# TSOC_Teensy3X.net
KiCad netlist of a schematic drawn in EAGLE
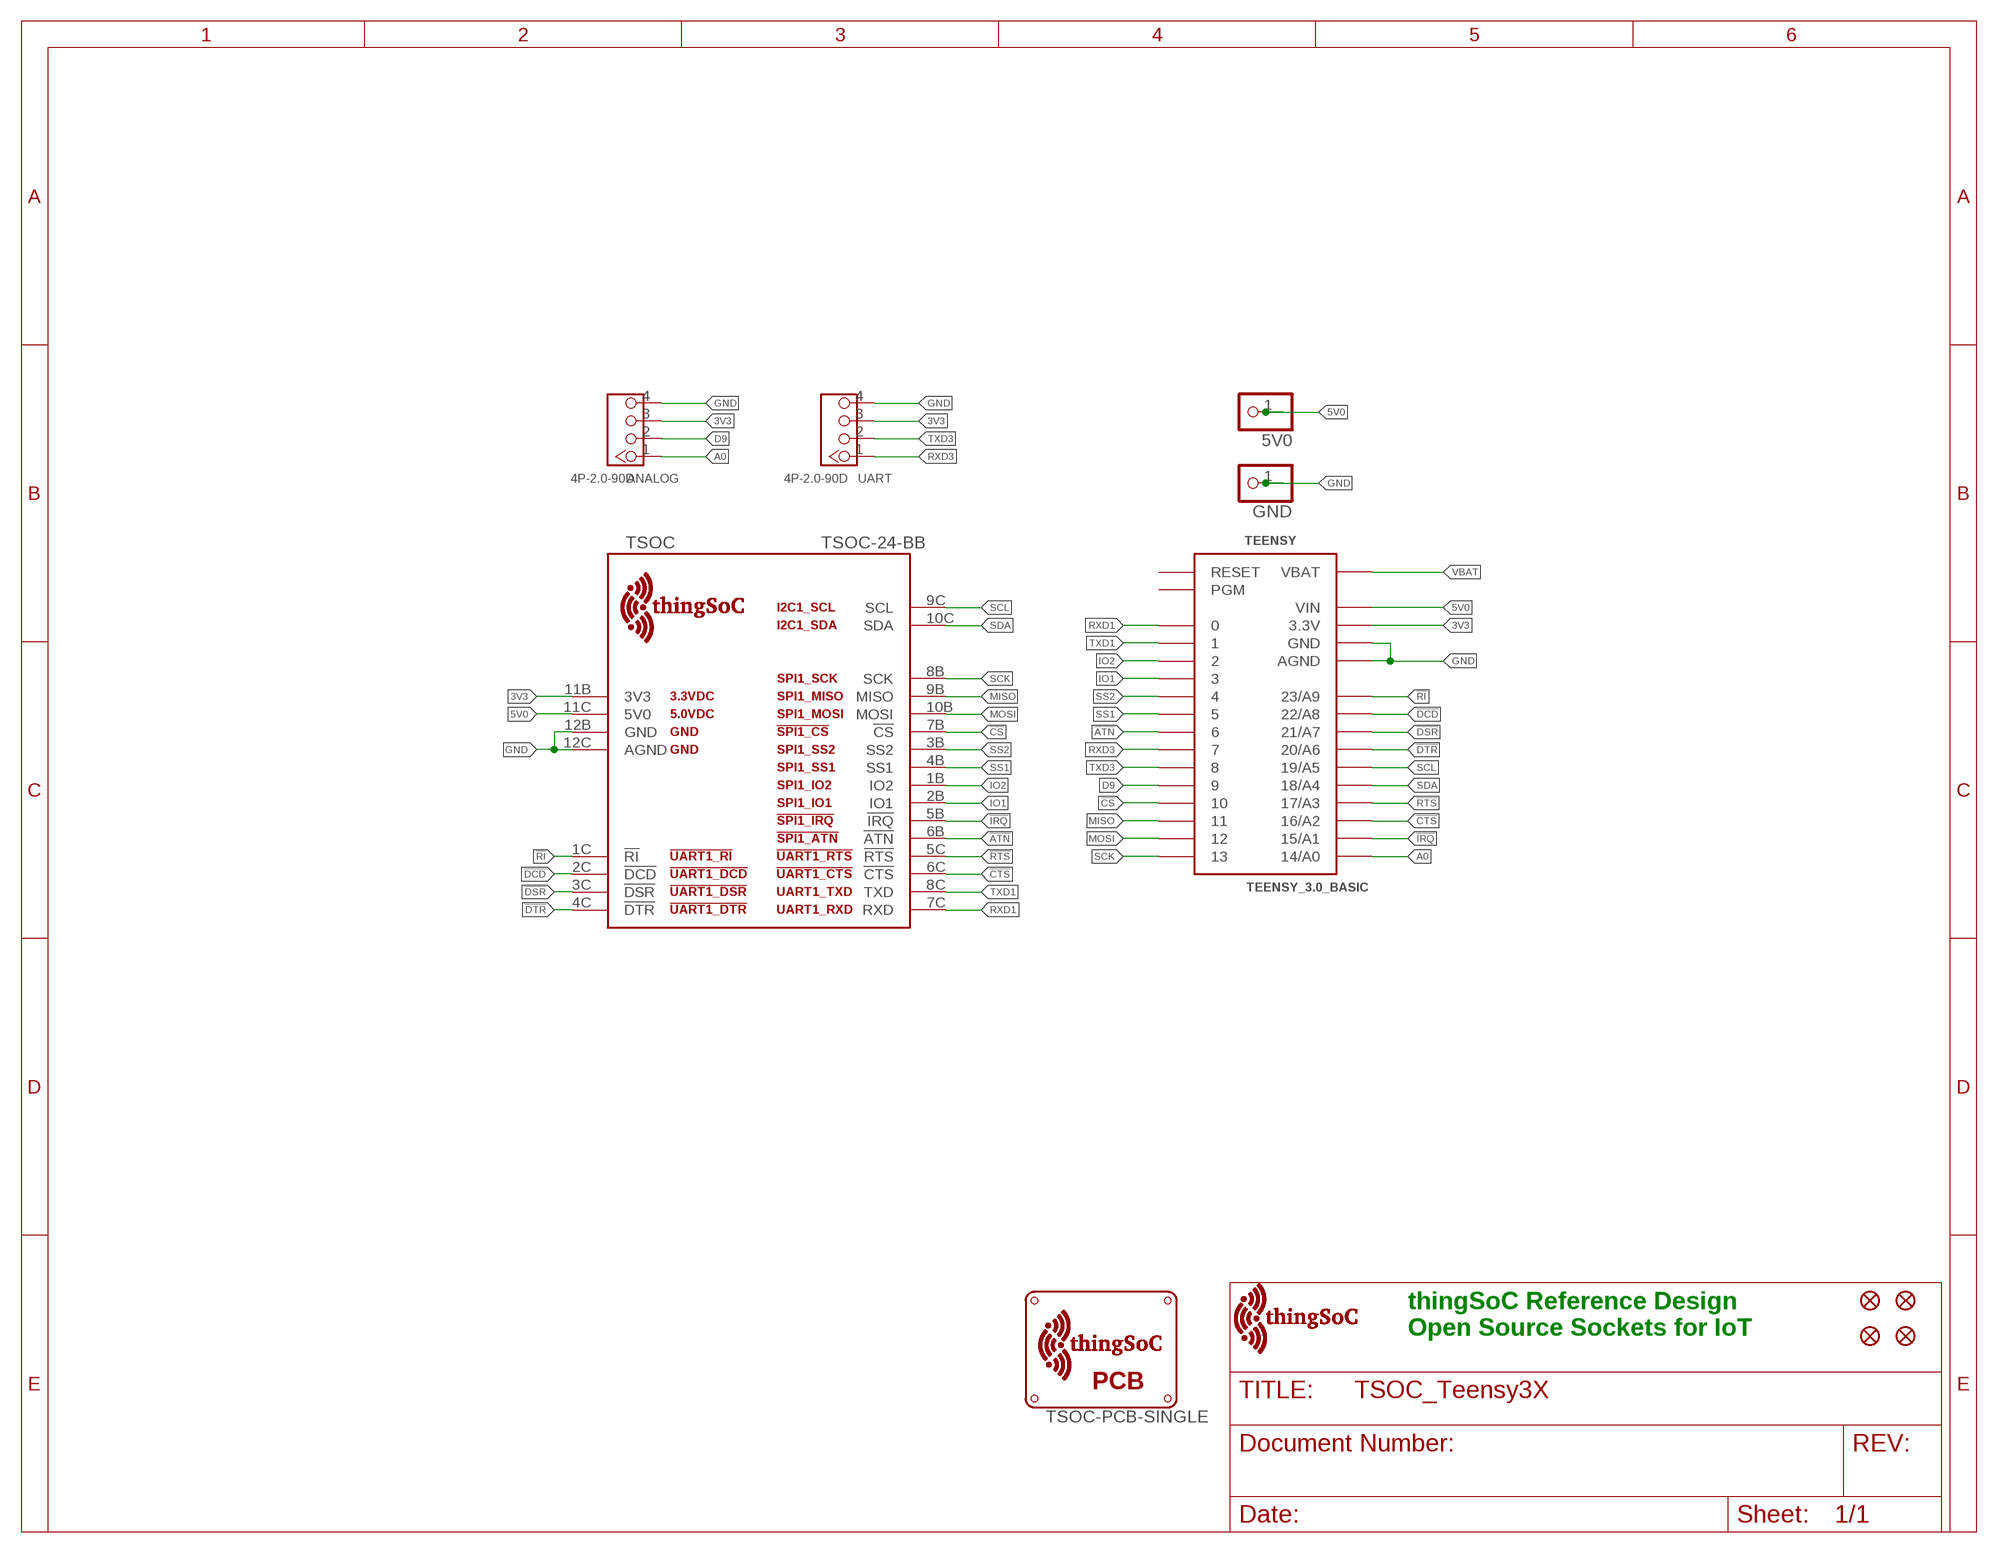
[diagram p0: schematic, sheet 1]

(export (version "E")
  (design (tool "Eeschema 10.0.6"))
  (components
    (comp (ref "5V0")
      (value "WPAD-1-PTH")
      (footprint "eagle-import:WPAD-1-PTH-2.54")
      (libsource (lib "eagle-import") (part "WPAD-1-PTH"))
    )
    (comp (ref "ANALOG")
      (value "4P-2.0-90D")
      (footprint "eagle-import:HW4-2.0-90D")
      (libsource (lib "eagle-import") (part "GROVE-CONNECTOR-DIP-90D(4P-2.0)"))
    )
    (comp (ref "FID1")
      (value "FIDUCIALUFIDUCIAL")
      (footprint "eagle-import:MICRO-FIDUCIAL")
      (libsource (lib "eagle-import") (part "FIDUCIALUFIDUCIAL"))
    )
    (comp (ref "FID2")
      (value "FIDUCIALUFIDUCIAL")
      (footprint "eagle-import:MICRO-FIDUCIAL")
      (libsource (lib "eagle-import") (part "FIDUCIALUFIDUCIAL"))
    )
    (comp (ref "FID3")
      (value "FIDUCIALUFIDUCIAL")
      (footprint "eagle-import:MICRO-FIDUCIAL")
      (libsource (lib "eagle-import") (part "FIDUCIALUFIDUCIAL"))
    )
    (comp (ref "FID4")
      (value "FIDUCIALUFIDUCIAL")
      (footprint "eagle-import:MICRO-FIDUCIAL")
      (libsource (lib "eagle-import") (part "FIDUCIALUFIDUCIAL"))
    )
    (comp (ref "GND")
      (value "WPAD-1-PTH")
      (footprint "eagle-import:WPAD-1-PTH-2.54")
      (libsource (lib "eagle-import") (part "WPAD-1-PTH"))
    )
    (comp (ref "TEENSY")
      (value "TEENSY_3.0_BASIC")
      (footprint "eagle-import:TEENSY_3.0_BASIC")
      (libsource (lib "eagle-import") (part "TEENSY_3.0_BASIC"))
    )
    (comp (ref "TSOC")
      (value "TSOC-24-BB")
      (footprint "eagle-import:TSOC-BB-S24")
      (libsource (lib "eagle-import") (part "TSOC-24-BB"))
    )
    (comp (ref "U$2")
      (value "TSOC-PCB-SINGLE")
      (footprint "eagle-import:TSOC-BB-BRD-DIM")
      (libsource (lib "eagle-import") (part "TSOC-PCB-SINGLE"))
    )
    (comp (ref "U$5")
      (value "TSOC-LOGO-LRG")
      (footprint "eagle-import:TSOC-LOGO-LRG")
      (libsource (lib "eagle-import") (part "TSOC-LOGO-LRG"))
    )
    (comp (ref "UART")
      (value "4P-2.0-90D")
      (footprint "eagle-import:HW4-2.0-90D")
      (libsource (lib "eagle-import") (part "GROVE-CONNECTOR-DIP-90D(4P-2.0)"))
    )
  )
  (nets
    (net (code "1") (name "/~{ATN}") (class "Default")
      (node (ref "TEENSY") (pin "6") (pinfunction "6_6") (pintype "bidirectional"))
      (node (ref "TSOC") (pin "6B") (pinfunction "~{ATN}_6B") (pintype "bidirectional"))
    )
    (net (code "2") (name "/~{CS}") (class "Default")
      (node (ref "TEENSY") (pin "10") (pinfunction "10_10") (pintype "bidirectional"))
      (node (ref "TSOC") (pin "7B") (pinfunction "~{CS}_7B") (pintype "bidirectional"))
    )
    (net (code "3") (name "/~{CTS}") (class "Default")
      (node (ref "TEENSY") (pin "16/A2") (pinfunction "16/A2_16/A2") (pintype "bidirectional"))
      (node (ref "TSOC") (pin "6C") (pinfunction "~{CTS}_6C") (pintype "bidirectional"))
    )
    (net (code "4") (name "/~{DCD}") (class "Default")
      (node (ref "TEENSY") (pin "22/A8") (pinfunction "22/A8_22/A8") (pintype "bidirectional"))
      (node (ref "TSOC") (pin "2C") (pinfunction "~{DCD}_2C") (pintype "bidirectional"))
    )
    (net (code "5") (name "/~{DSR}") (class "Default")
      (node (ref "TEENSY") (pin "21/A7") (pinfunction "21/A7_21/A7") (pintype "bidirectional"))
      (node (ref "TSOC") (pin "3C") (pinfunction "~{DSR}_3C") (pintype "bidirectional"))
    )
    (net (code "6") (name "/~{DTR}") (class "Default")
      (node (ref "TEENSY") (pin "20/A6") (pinfunction "20/A6_20/A6") (pintype "bidirectional"))
      (node (ref "TSOC") (pin "4C") (pinfunction "~{DTR}_4C") (pintype "bidirectional"))
    )
    (net (code "7") (name "/~{IRQ}") (class "Default")
      (node (ref "TEENSY") (pin "15/A1") (pinfunction "15/A1_15/A1") (pintype "bidirectional"))
      (node (ref "TSOC") (pin "5B") (pinfunction "~{IRQ}_5B") (pintype "bidirectional"))
    )
    (net (code "8") (name "/~{RI}") (class "Default")
      (node (ref "TEENSY") (pin "23/A9") (pinfunction "23/A9_23/A9") (pintype "bidirectional"))
      (node (ref "TSOC") (pin "1C") (pinfunction "~{RI}_1C") (pintype "bidirectional"))
    )
    (net (code "9") (name "/~{RTS}") (class "Default")
      (node (ref "TEENSY") (pin "17/A3") (pinfunction "17/A3_17/A3") (pintype "bidirectional"))
      (node (ref "TSOC") (pin "5C") (pinfunction "~{RTS}_5C") (pintype "bidirectional"))
    )
    (net (code "10") (name "3V3") (class "Default")
      (node (ref "ANALOG") (pin "3") (pinfunction "3_3") (pintype "bidirectional"))
      (node (ref "TEENSY") (pin "3.3V") (pinfunction "3.3V_3.3V") (pintype "power_in"))
      (node (ref "TEENSY") (pin "3.3V1") (pinfunction "3.3V_3.3V1") (pintype "power_in"))
      (node (ref "TSOC") (pin "11B") (pinfunction "3V3_11B") (pintype "bidirectional"))
      (node (ref "UART") (pin "3") (pinfunction "3_3") (pintype "bidirectional"))
    )
    (net (code "11") (name "5V0") (class "Default")
      (node (ref "5V0") (pin "1") (pinfunction "1_1") (pintype "passive"))
      (node (ref "TEENSY") (pin "VIN") (pinfunction "VIN_VIN") (pintype "power_in"))
      (node (ref "TSOC") (pin "11C") (pinfunction "5V0_11C") (pintype "bidirectional"))
    )
    (net (code "12") (name "A0") (class "Default")
      (node (ref "ANALOG") (pin "1") (pinfunction "1_1") (pintype "bidirectional"))
      (node (ref "TEENSY") (pin "14/A0") (pinfunction "14/A0_14/A0") (pintype "bidirectional"))
    )
    (net (code "13") (name "D9") (class "Default")
      (node (ref "ANALOG") (pin "2") (pinfunction "2_2") (pintype "bidirectional"))
      (node (ref "TEENSY") (pin "9") (pinfunction "9_9") (pintype "bidirectional"))
    )
    (net (code "14") (name "GND") (class "Default")
      (node (ref "ANALOG") (pin "4") (pinfunction "4_4") (pintype "bidirectional"))
      (node (ref "GND") (pin "1") (pinfunction "1_1") (pintype "passive"))
      (node (ref "TEENSY") (pin "AGND") (pinfunction "AGND_AGND") (pintype "power_in"))
      (node (ref "TEENSY") (pin "GND") (pinfunction "GND_GND") (pintype "power_in"))
      (node (ref "TEENSY") (pin "GND1") (pinfunction "GND_GND1") (pintype "power_in"))
      (node (ref "TSOC") (pin "12B") (pinfunction "GND_12B") (pintype "bidirectional"))
      (node (ref "TSOC") (pin "12C") (pinfunction "AGND_12C") (pintype "bidirectional"))
      (node (ref "UART") (pin "4") (pinfunction "4_4") (pintype "bidirectional"))
    )
    (net (code "15") (name "IO1") (class "Default")
      (node (ref "TEENSY") (pin "3") (pinfunction "3_3") (pintype "bidirectional"))
      (node (ref "TSOC") (pin "2B") (pinfunction "IO1_2B") (pintype "bidirectional"))
    )
    (net (code "16") (name "IO2") (class "Default")
      (node (ref "TEENSY") (pin "2") (pinfunction "2_2") (pintype "bidirectional"))
      (node (ref "TSOC") (pin "1B") (pinfunction "IO2_1B") (pintype "bidirectional"))
    )
    (net (code "17") (name "MISO") (class "Default")
      (node (ref "TEENSY") (pin "11") (pinfunction "11_11") (pintype "bidirectional"))
      (node (ref "TSOC") (pin "9B") (pinfunction "MISO_9B") (pintype "bidirectional"))
    )
    (net (code "18") (name "MOSI") (class "Default")
      (node (ref "TEENSY") (pin "12") (pinfunction "12_12") (pintype "bidirectional"))
      (node (ref "TSOC") (pin "10B") (pinfunction "MOSI_10B") (pintype "bidirectional"))
    )
    (net (code "19") (name "RXD1") (class "Default")
      (node (ref "TEENSY") (pin "0") (pinfunction "0_0") (pintype "bidirectional"))
      (node (ref "TSOC") (pin "7C") (pinfunction "RXD_7C") (pintype "bidirectional"))
    )
    (net (code "20") (name "RXD3") (class "Default")
      (node (ref "TEENSY") (pin "7") (pinfunction "7_7") (pintype "bidirectional"))
      (node (ref "UART") (pin "1") (pinfunction "1_1") (pintype "bidirectional"))
    )
    (net (code "21") (name "SCK") (class "Default")
      (node (ref "TEENSY") (pin "13") (pinfunction "13_13") (pintype "bidirectional"))
      (node (ref "TSOC") (pin "8B") (pinfunction "SCK_8B") (pintype "bidirectional"))
    )
    (net (code "22") (name "SCL") (class "Default")
      (node (ref "TEENSY") (pin "19/A5") (pinfunction "19/A5_19/A5") (pintype "bidirectional"))
      (node (ref "TSOC") (pin "9C") (pinfunction "SCL_9C") (pintype "bidirectional"))
    )
    (net (code "23") (name "SDA") (class "Default")
      (node (ref "TEENSY") (pin "18/A4") (pinfunction "18/A4_18/A4") (pintype "bidirectional"))
      (node (ref "TSOC") (pin "10C") (pinfunction "SDA_10C") (pintype "bidirectional"))
    )
    (net (code "24") (name "SS1") (class "Default")
      (node (ref "TEENSY") (pin "5") (pinfunction "5_5") (pintype "bidirectional"))
      (node (ref "TSOC") (pin "4B") (pinfunction "SS1_4B") (pintype "bidirectional"))
    )
    (net (code "25") (name "SS2") (class "Default")
      (node (ref "TEENSY") (pin "4") (pinfunction "4_4") (pintype "bidirectional"))
      (node (ref "TSOC") (pin "3B") (pinfunction "SS2_3B") (pintype "bidirectional"))
    )
    (net (code "26") (name "TXD1") (class "Default")
      (node (ref "TEENSY") (pin "1") (pinfunction "1_1") (pintype "bidirectional"))
      (node (ref "TSOC") (pin "8C") (pinfunction "TXD_8C") (pintype "bidirectional"))
    )
    (net (code "27") (name "TXD3") (class "Default")
      (node (ref "TEENSY") (pin "8") (pinfunction "8_8") (pintype "bidirectional"))
      (node (ref "UART") (pin "2") (pinfunction "2_2") (pintype "bidirectional"))
    )
    (net (code "28") (name "VBAT") (class "Default")
      (node (ref "TEENSY") (pin "VBAT") (pinfunction "VBAT_VBAT") (pintype "power_in"))
    )
    (net (code "29") (name "unconnected-(TEENSY-PadPGM)") (class "Default")
      (node (ref "TEENSY") (pin "PGM") (pinfunction "PGM_PGM") (pintype "bidirectional"))
    )
    (net (code "30") (name "unconnected-(TEENSY-PadRESET)") (class "Default")
      (node (ref "TEENSY") (pin "RESET") (pinfunction "RESET_RESET") (pintype "bidirectional"))
    )
  )
)
